# breakout_mdbt40.net
KiCad netlist of a schematic drawn in EAGLE
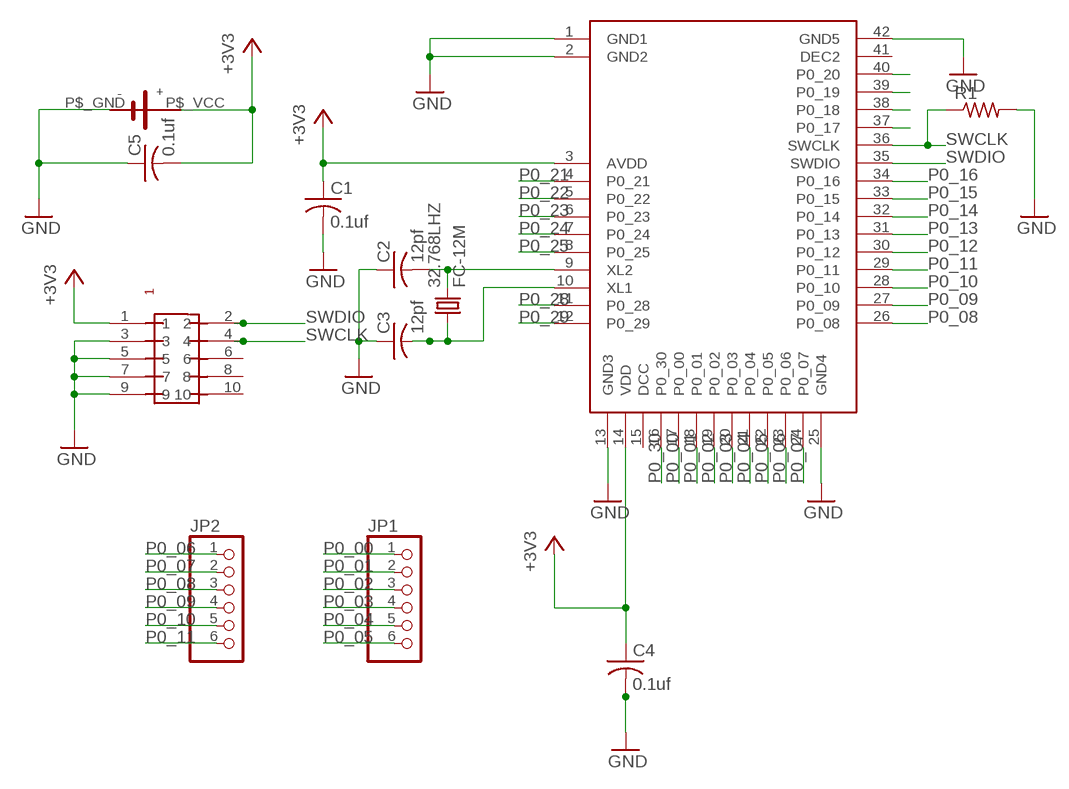
[diagram p0: schematic, sheet 1]

(export (version "E")
  (design (tool "Eeschema 10.0.6"))
  (components
    (comp (ref "32.768LHZ")
      (value "FC-12M")
      (footprint "eagle-import:FC-12M")
      (libsource (lib "eagle-import") (part "FC-12M"))
    )
    (comp (ref "C1")
      (value "0.1uf")
      (footprint "eagle-import:C0603")
      (libsource (lib "eagle-import") (part "C-USC0603"))
    )
    (comp (ref "C2")
      (value "12pf")
      (footprint "eagle-import:C0603")
      (libsource (lib "eagle-import") (part "C-USC0603"))
    )
    (comp (ref "C3")
      (value "12pf")
      (footprint "eagle-import:C0603")
      (libsource (lib "eagle-import") (part "C-USC0603"))
    )
    (comp (ref "C4")
      (value "0.1uf")
      (footprint "eagle-import:C0603")
      (libsource (lib "eagle-import") (part "C-USC0603"))
    )
    (comp (ref "C5")
      (value "0.1uf")
      (footprint "eagle-import:C0603")
      (libsource (lib "eagle-import") (part "C-USC0603"))
    )
    (comp (ref "JP1")
      (value "PINHD-1X6")
      (footprint "eagle-import:1X06")
      (libsource (lib "eagle-import") (part "PINHD-1X6"))
    )
    (comp (ref "JP2")
      (value "PINHD-1X6")
      (footprint "eagle-import:1X06")
      (libsource (lib "eagle-import") (part "PINHD-1X6"))
    )
    (comp (ref "R1")
      (value "R-US_R0603")
      (footprint "eagle-import:R0603")
      (libsource (lib "eagle-import") (part "R-US_R0603"))
    )
    (comp (ref "U$1")
      (value "RAYTAC-MDBT40")
      (footprint "eagle-import:RAYTAC-MDBT40")
      (libsource (lib "eagle-import") (part "RAYTAC-MDBT40"))
    )
    (comp (ref "U$2")
      (value "PIN-HEADER-SMT(1.27MM)2X5")
      (footprint "eagle-import:PIN-HEADER-SMT(1.27MM)2X5")
      (libsource (lib "eagle-import") (part "PIN-HEADER-SMT(1.27MM)2X5"))
    )
    (comp (ref "U$3")
      (value "SMTU2450-BOTTOM-MINI")
      (footprint "eagle-import:SMTU2450-BOTTOM-MINI")
      (libsource (lib "eagle-import") (part "SMTU2450-BOTTOM-MINI"))
    )
  )
  (nets
    (net (code "1") (name "+3V3") (class "Default")
      (node (ref "C1") (pin "1") (pinfunction "1_1") (pintype "passive"))
      (node (ref "C4") (pin "1") (pinfunction "1_1") (pintype "passive"))
      (node (ref "C5") (pin "2") (pinfunction "2_2") (pintype "passive"))
      (node (ref "U$1") (pin "14") (pinfunction "VDD_14") (pintype "bidirectional"))
      (node (ref "U$1") (pin "3") (pinfunction "AVDD_3") (pintype "bidirectional"))
      (node (ref "U$2") (pin "1") (pinfunction "1_1") (pintype "bidirectional"))
      (node (ref "U$3") (pin "P$_VCC") (pinfunction "P$_VCC_P$_VCC") (pintype "bidirectional"))
    )
    (net (code "2") (name "/P0_00") (class "Default")
      (node (ref "JP1") (pin "1") (pinfunction "1_1") (pintype "passive"))
      (node (ref "U$1") (pin "17") (pinfunction "P0_00_17") (pintype "bidirectional"))
    )
    (net (code "3") (name "/P0_01") (class "Default")
      (node (ref "JP1") (pin "2") (pinfunction "2_2") (pintype "passive"))
      (node (ref "U$1") (pin "18") (pinfunction "P0_01_18") (pintype "bidirectional"))
    )
    (net (code "4") (name "/P0_02") (class "Default")
      (node (ref "JP1") (pin "3") (pinfunction "3_3") (pintype "passive"))
      (node (ref "U$1") (pin "19") (pinfunction "P0_02_19") (pintype "bidirectional"))
    )
    (net (code "5") (name "/P0_03") (class "Default")
      (node (ref "JP1") (pin "4") (pinfunction "4_4") (pintype "passive"))
      (node (ref "U$1") (pin "20") (pinfunction "P0_03_20") (pintype "bidirectional"))
    )
    (net (code "6") (name "/P0_04") (class "Default")
      (node (ref "JP1") (pin "5") (pinfunction "5_5") (pintype "passive"))
      (node (ref "U$1") (pin "21") (pinfunction "P0_04_21") (pintype "bidirectional"))
    )
    (net (code "7") (name "/P0_05") (class "Default")
      (node (ref "JP1") (pin "6") (pinfunction "6_6") (pintype "passive"))
      (node (ref "U$1") (pin "22") (pinfunction "P0_05_22") (pintype "bidirectional"))
    )
    (net (code "8") (name "/P0_06") (class "Default")
      (node (ref "JP2") (pin "1") (pinfunction "1_1") (pintype "passive"))
      (node (ref "U$1") (pin "23") (pinfunction "P0_06_23") (pintype "bidirectional"))
    )
    (net (code "9") (name "/P0_07") (class "Default")
      (node (ref "JP2") (pin "2") (pinfunction "2_2") (pintype "passive"))
      (node (ref "U$1") (pin "24") (pinfunction "P0_07_24") (pintype "bidirectional"))
    )
    (net (code "10") (name "/P0_08") (class "Default")
      (node (ref "JP2") (pin "3") (pinfunction "3_3") (pintype "passive"))
      (node (ref "U$1") (pin "26") (pinfunction "P0_08_26") (pintype "bidirectional"))
    )
    (net (code "11") (name "/P0_09") (class "Default")
      (node (ref "JP2") (pin "4") (pinfunction "4_4") (pintype "passive"))
      (node (ref "U$1") (pin "27") (pinfunction "P0_09_27") (pintype "bidirectional"))
    )
    (net (code "12") (name "/P0_10") (class "Default")
      (node (ref "JP2") (pin "5") (pinfunction "5_5") (pintype "passive"))
      (node (ref "U$1") (pin "28") (pinfunction "P0_10_28") (pintype "bidirectional"))
    )
    (net (code "13") (name "/P0_11") (class "Default")
      (node (ref "JP2") (pin "6") (pinfunction "6_6") (pintype "passive"))
      (node (ref "U$1") (pin "29") (pinfunction "P0_11_29") (pintype "bidirectional"))
    )
    (net (code "14") (name "/P0_12") (class "Default")
      (node (ref "U$1") (pin "30") (pinfunction "P0_12_30") (pintype "bidirectional"))
    )
    (net (code "15") (name "/P0_13") (class "Default")
      (node (ref "U$1") (pin "31") (pinfunction "P0_13_31") (pintype "bidirectional"))
    )
    (net (code "16") (name "/P0_14") (class "Default")
      (node (ref "U$1") (pin "32") (pinfunction "P0_14_32") (pintype "bidirectional"))
    )
    (net (code "17") (name "/P0_15") (class "Default")
      (node (ref "U$1") (pin "33") (pinfunction "P0_15_33") (pintype "bidirectional"))
    )
    (net (code "18") (name "/P0_16") (class "Default")
      (node (ref "U$1") (pin "34") (pinfunction "P0_16_34") (pintype "bidirectional"))
    )
    (net (code "19") (name "/P0_21") (class "Default")
      (node (ref "U$1") (pin "4") (pinfunction "P0_21_4") (pintype "bidirectional"))
    )
    (net (code "20") (name "/P0_22") (class "Default")
      (node (ref "U$1") (pin "5") (pinfunction "P0_22_5") (pintype "bidirectional"))
    )
    (net (code "21") (name "/P0_23") (class "Default")
      (node (ref "U$1") (pin "6") (pinfunction "P0_23_6") (pintype "bidirectional"))
    )
    (net (code "22") (name "/P0_24") (class "Default")
      (node (ref "U$1") (pin "7") (pinfunction "P0_24_7") (pintype "bidirectional"))
    )
    (net (code "23") (name "/P0_25") (class "Default")
      (node (ref "U$1") (pin "8") (pinfunction "P0_25_8") (pintype "bidirectional"))
    )
    (net (code "24") (name "/P0_28") (class "Default")
      (node (ref "U$1") (pin "11") (pinfunction "P0_28_11") (pintype "bidirectional"))
    )
    (net (code "25") (name "/P0_29") (class "Default")
      (node (ref "U$1") (pin "12") (pinfunction "P0_29_12") (pintype "bidirectional"))
    )
    (net (code "26") (name "/P0_30") (class "Default")
      (node (ref "U$1") (pin "16") (pinfunction "P0_30_16") (pintype "bidirectional"))
    )
    (net (code "27") (name "/SWCLK") (class "Default")
      (node (ref "R1") (pin "1") (pinfunction "1_1") (pintype "passive"))
      (node (ref "U$1") (pin "36") (pinfunction "SWCLK_36") (pintype "bidirectional"))
      (node (ref "U$2") (pin "4") (pinfunction "4_4") (pintype "bidirectional"))
    )
    (net (code "28") (name "/SWDIO") (class "Default")
      (node (ref "U$1") (pin "35") (pinfunction "SWDIO_35") (pintype "bidirectional"))
      (node (ref "U$2") (pin "2") (pinfunction "2_2") (pintype "bidirectional"))
    )
    (net (code "29") (name "GND") (class "Default")
      (node (ref "C1") (pin "2") (pinfunction "2_2") (pintype "passive"))
      (node (ref "C2") (pin "1") (pinfunction "1_1") (pintype "passive"))
      (node (ref "C3") (pin "1") (pinfunction "1_1") (pintype "passive"))
      (node (ref "C4") (pin "2") (pinfunction "2_2") (pintype "passive"))
      (node (ref "C5") (pin "1") (pinfunction "1_1") (pintype "passive"))
      (node (ref "R1") (pin "2") (pinfunction "2_2") (pintype "passive"))
      (node (ref "U$1") (pin "1") (pinfunction "GND1_1") (pintype "bidirectional"))
      (node (ref "U$1") (pin "13") (pinfunction "GND3_13") (pintype "bidirectional"))
      (node (ref "U$1") (pin "2") (pinfunction "GND2_2") (pintype "bidirectional"))
      (node (ref "U$1") (pin "25") (pinfunction "GND4_25") (pintype "bidirectional"))
      (node (ref "U$1") (pin "42") (pinfunction "GND5_42") (pintype "bidirectional"))
      (node (ref "U$2") (pin "3") (pinfunction "3_3") (pintype "bidirectional"))
      (node (ref "U$2") (pin "5") (pinfunction "5_5") (pintype "bidirectional"))
      (node (ref "U$2") (pin "7") (pinfunction "7_7") (pintype "bidirectional"))
      (node (ref "U$2") (pin "9") (pinfunction "9_9") (pintype "bidirectional"))
      (node (ref "U$3") (pin "P$_GND") (pinfunction "P$_GND_P$_GND") (pintype "bidirectional"))
    )
    (net (code "30") (name "Net-(U$1-XL1)") (class "Default")
      (node (ref "32.768LHZ") (pin "1") (pinfunction "1_1") (pintype "passive"))
      (node (ref "C3") (pin "2") (pinfunction "2_2") (pintype "passive"))
      (node (ref "U$1") (pin "10") (pinfunction "XL1_10") (pintype "bidirectional"))
    )
    (net (code "31") (name "Net-(U$1-XL2)") (class "Default")
      (node (ref "32.768LHZ") (pin "2") (pinfunction "2_2") (pintype "passive"))
      (node (ref "C2") (pin "2") (pinfunction "2_2") (pintype "passive"))
      (node (ref "U$1") (pin "9") (pinfunction "XL2_9") (pintype "bidirectional"))
    )
    (net (code "32") (name "unconnected-(U$1-DCC-Pad15)") (class "Default")
      (node (ref "U$1") (pin "15") (pinfunction "DCC_15") (pintype "bidirectional"))
    )
    (net (code "33") (name "unconnected-(U$1-DEC2-Pad41)") (class "Default")
      (node (ref "U$1") (pin "41") (pinfunction "DEC2_41") (pintype "bidirectional"))
    )
    (net (code "34") (name "unconnected-(U$1-P0_17-Pad37)") (class "Default")
      (node (ref "U$1") (pin "37") (pinfunction "P0_17_37") (pintype "bidirectional"))
    )
    (net (code "35") (name "unconnected-(U$1-P0_18-Pad38)") (class "Default")
      (node (ref "U$1") (pin "38") (pinfunction "P0_18_38") (pintype "bidirectional"))
    )
    (net (code "36") (name "unconnected-(U$1-P0_19-Pad39)") (class "Default")
      (node (ref "U$1") (pin "39") (pinfunction "P0_19_39") (pintype "bidirectional"))
    )
    (net (code "37") (name "unconnected-(U$1-P0_20-Pad40)") (class "Default")
      (node (ref "U$1") (pin "40") (pinfunction "P0_20_40") (pintype "bidirectional"))
    )
    (net (code "38") (name "unconnected-(U$2-Pad6)") (class "Default")
      (node (ref "U$2") (pin "6") (pinfunction "6_6") (pintype "bidirectional"))
    )
    (net (code "39") (name "unconnected-(U$2-Pad8)") (class "Default")
      (node (ref "U$2") (pin "8") (pinfunction "8_8") (pintype "bidirectional"))
    )
    (net (code "40") (name "unconnected-(U$2-Pad10)") (class "Default")
      (node (ref "U$2") (pin "10") (pinfunction "10_10") (pintype "bidirectional"))
    )
  )
)
